# RC_Transmitter_RX_v42.net
KiCad netlist of a schematic drawn in EAGLE
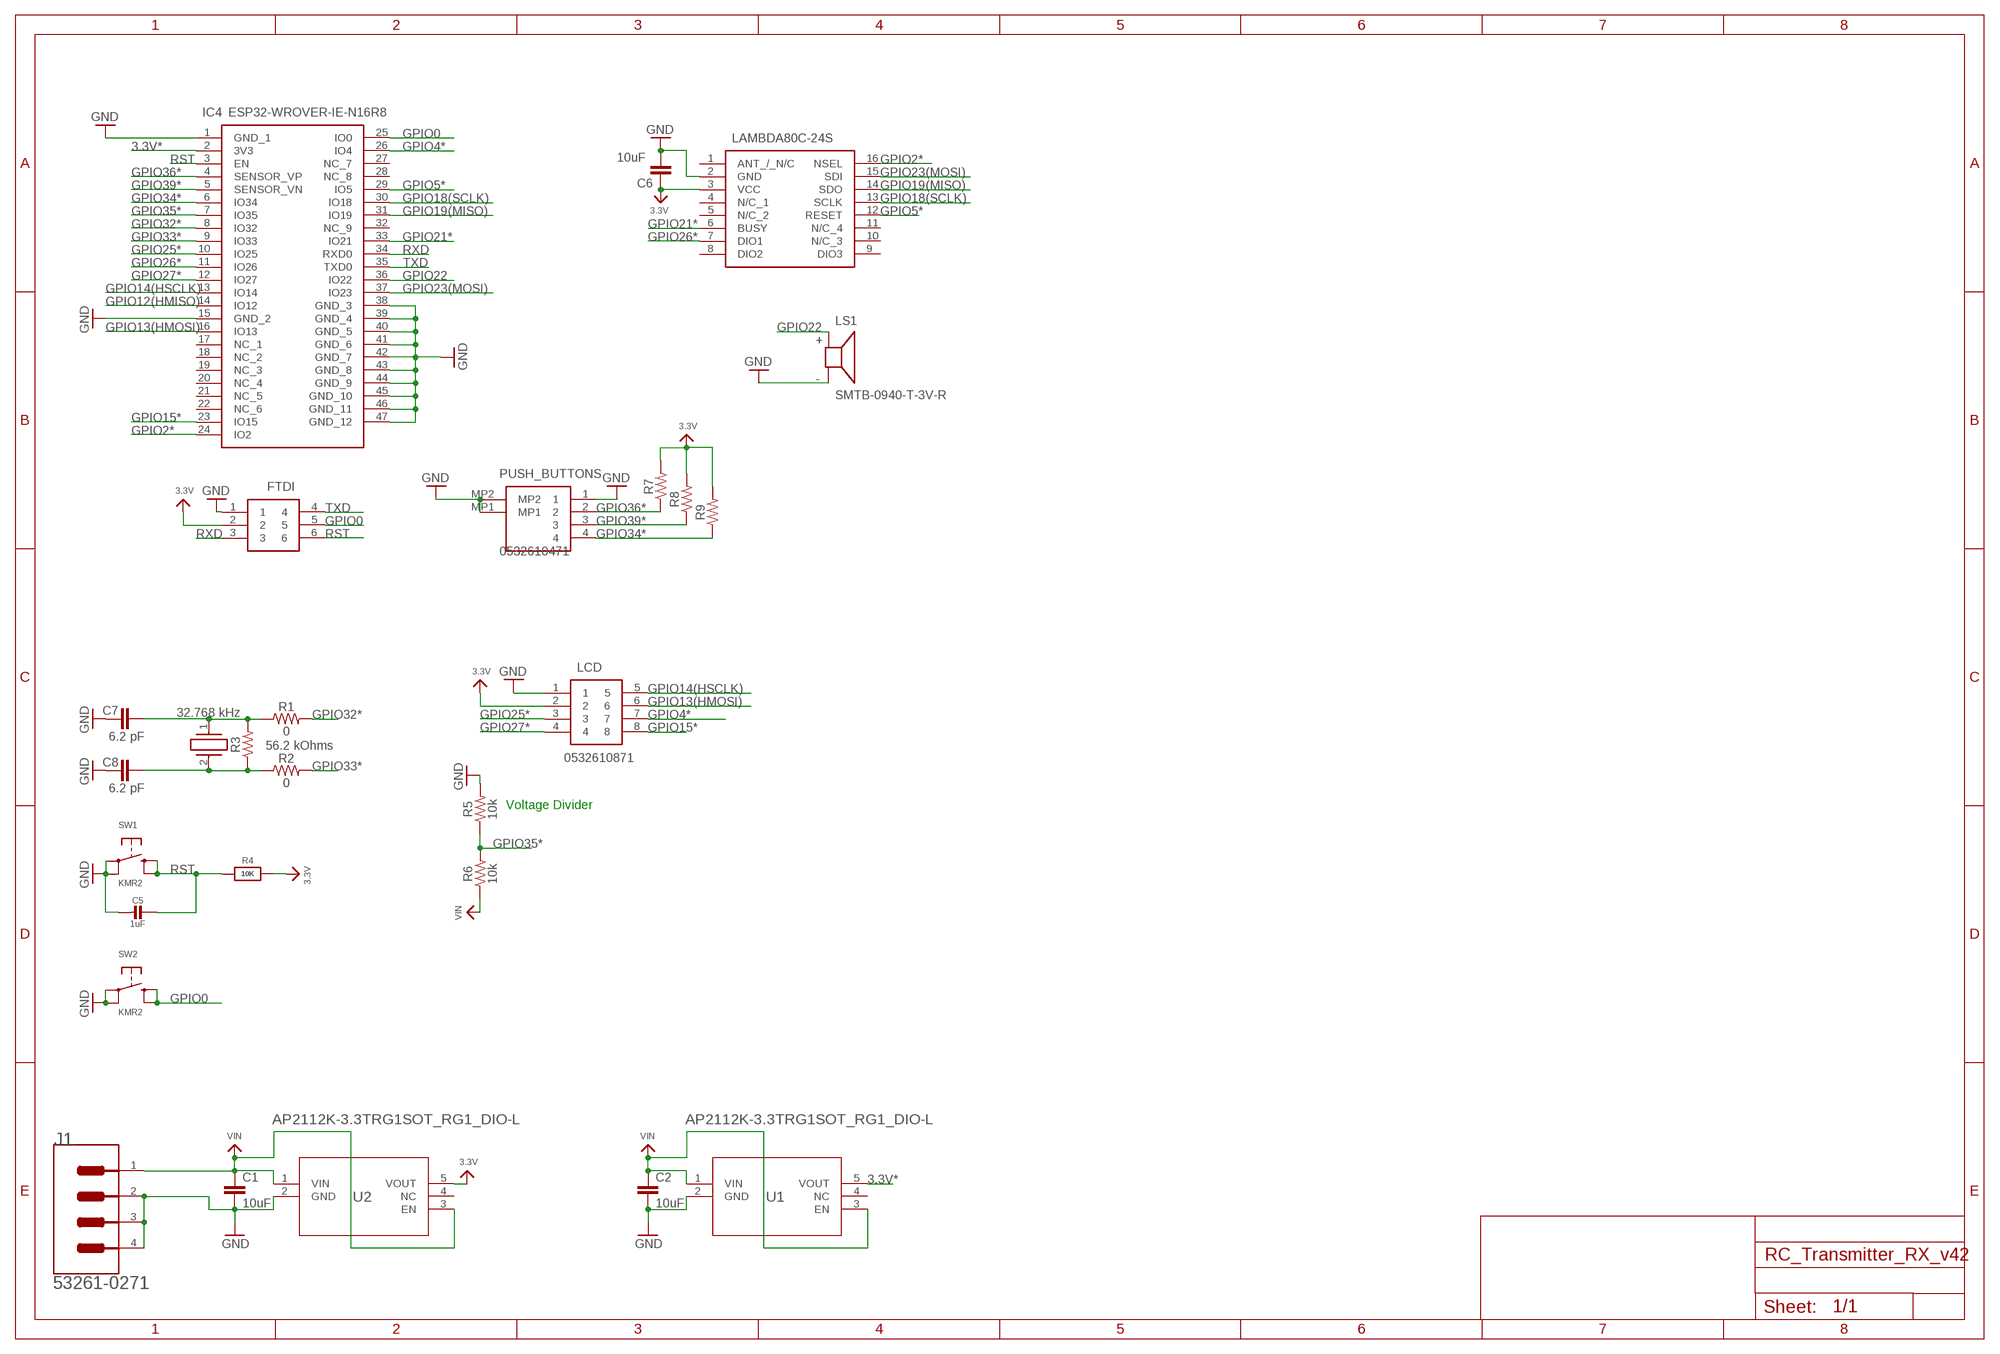
[diagram p0: schematic, sheet 1]

(export (version "E")
  (design (tool "Eeschema 10.0.6"))
  (components
    (comp (ref "C1")
      (value "10uF")
      (footprint "eagle-import:0805")
      (libsource (lib "eagle-import") (part "10UF-0805-10V-10%"))
    )
    (comp (ref "C2")
      (value "10uF")
      (footprint "eagle-import:0805")
      (libsource (lib "eagle-import") (part "10UF-0805-10V-10%"))
    )
    (comp (ref "C5")
      (value "1uF")
      (footprint "eagle-import:0805-NO")
      (libsource (lib "eagle-import") (part "CAP_CERAMIC0805-NOOUTLINE"))
    )
    (comp (ref "C6")
      (value "10uF")
      (footprint "eagle-import:0805")
      (libsource (lib "eagle-import") (part "10UF-0805-10V-10%"))
    )
    (comp (ref "C7")
      (value "6.2 pF")
      (footprint "eagle-import:CAPC2012X110")
      (libsource (lib "eagle-import") (part "CCHIP-0805(2012-METRIC)_"))
    )
    (comp (ref "C8")
      (value "6.2 pF")
      (footprint "eagle-import:CAPC2012X110")
      (libsource (lib "eagle-import") (part "CCHIP-0805(2012-METRIC)_"))
    )
    (comp (ref "CRYSTAL")
      (value "32.768 kHz")
      (footprint "eagle-import:ECX327CDX1293")
      (fields
        (field (name "ARROW_PART_NUMBER") "ECX-.327-CDX-1293")
        (field (name "MOUSER_PART_NUMBER") "520-ECX-.327CDX-1293")
        (field (name "ARROW_PART_NUMBER_1") "Crystal")
      )
      (libsource (lib "eagle-import") (part "ECX-.327-CDX-1293"))
    )
    (comp (ref "FTDI")
      (value "0532610671")
      (footprint "eagle-import:0532610671")
      (libsource (lib "eagle-import") (part "0532610671"))
    )
    (comp (ref "IC1")
      (value "LAMBDA80C-24S")
      (footprint "eagle-import:LAMBDA80C24S")
      (fields (field (name "MOUSER_PART_NUMBER") "223-LAMBDA80C-24S"))
      (libsource (lib "eagle-import") (part "LAMBDA80C-24S"))
    )
    (comp (ref "IC4")
      (value "ESP32-WROVER-IE-N16R8")
      (footprint "eagle-import:ESP32WROVERIEN16R8")
      (fields
        (field (name "MANUFACTURER_PART_NUMBER") "ESP32-Wrover-IE-N16R8")
        (field (name "MOUSER_PART_NUMBER") "356-ESP32WRVIE2864UC")
      )
      (libsource (lib "eagle-import") (part "ESP32-WROVER-IE-N16R8"))
    )
    (comp (ref "J1")
      (value "MOLEX_53261-0271MOLEX_53261-0271_0_0")
      (footprint "eagle-import:MOLEX_53261-0271_0")
      (fields
        (field (name "DIGIKEY_PART_NUMBER") "WM7620CT-ND")
        (field (name "MF") "Molex")
        (field (name "MOUSER_PART_NUMBER") "538-53261-0271")
      )
      (libsource (lib "eagle-import") (part "MOLEX_53261-0271MOLEX_53261-0271_0_0"))
    )
    (comp (ref "LCD")
      (value "0532610871")
      (footprint "eagle-import:53261-0871")
      (libsource (lib "eagle-import") (part "0532610871"))
    )
    (comp (ref "LS1")
      (value "SMTB-0940-T-3V-R")
      (footprint "eagle-import:XDCR_SMTB-0940-T-3V-R")
      (fields (field (name "MF") "PUI Audio, Inc."))
      (libsource (lib "eagle-import") (part "SMTB-0940-T-3V-R"))
    )
    (comp (ref "PUSH_BUTTONS")
      (value "0532610471")
      (footprint "eagle-import:0532610471")
      (libsource (lib "eagle-import") (part "0532610471"))
    )
    (comp (ref "R1")
      (value "0")
      (footprint "eagle-import:0603")
      (libsource (lib "eagle-import") (part "0OHM-0603-1/10W-5%"))
    )
    (comp (ref "R2")
      (value "0")
      (footprint "eagle-import:0603")
      (libsource (lib "eagle-import") (part "0OHM-0603-1/10W-5%"))
    )
    (comp (ref "R3")
      (value "56.2 kOhms")
      (footprint "eagle-import:0603")
      (libsource (lib "eagle-import") (part "0OHM-0603-1/10W-5%"))
    )
    (comp (ref "R4")
      (value "10K")
      (footprint "eagle-import:_0805")
      (libsource (lib "eagle-import") (part "RESISTOR_0805"))
    )
    (comp (ref "R5")
      (value "10k")
      (footprint "eagle-import:0603")
      (libsource (lib "eagle-import") (part "0OHM-0603-1/10W-5%"))
    )
    (comp (ref "R6")
      (value "10k")
      (footprint "eagle-import:0603")
      (libsource (lib "eagle-import") (part "0OHM-0603-1/10W-5%"))
    )
    (comp (ref "R7")
      (value "0")
      (footprint "eagle-import:0603")
      (libsource (lib "eagle-import") (part "0OHM-0603-1/10W-5%"))
    )
    (comp (ref "R8")
      (value "0")
      (footprint "eagle-import:0603")
      (libsource (lib "eagle-import") (part "0OHM-0603-1/10W-5%"))
    )
    (comp (ref "R9")
      (value "0")
      (footprint "eagle-import:0603")
      (libsource (lib "eagle-import") (part "0OHM-0603-1/10W-5%"))
    )
    (comp (ref "SW1")
      (value "KMR2")
      (footprint "eagle-import:BTN_KMR2_4.6X2.8")
      (libsource (lib "eagle-import") (part "SWITCH_TACT_SMT4.6X2.8"))
    )
    (comp (ref "SW2")
      (value "KMR2")
      (footprint "eagle-import:BTN_KMR2_4.6X2.8")
      (libsource (lib "eagle-import") (part "SWITCH_TACT_SMT4.6X2.8"))
    )
    (comp (ref "U1")
      (value "AP2112K-3.3TRG1SOT_RG1_DIO-L")
      (footprint "eagle-import:SOT_RG1_DIO-L")
      (fields
        (field (name "MANUFACTURER_PART_NUMBER") "AP2112K-3.3TRG1")
        (field (name "COPYRIGHT") "Copyright (C) 2023 Ultra Librarian. All rights reserved.")
      )
      (libsource (lib "eagle-import") (part "AP2112K-3.3TRG1SOT_RG1_DIO-L"))
    )
    (comp (ref "U2")
      (value "AP2112K-3.3TRG1SOT_RG1_DIO-L")
      (footprint "eagle-import:SOT_RG1_DIO-L")
      (fields
        (field (name "MANUFACTURER_PART_NUMBER") "AP2112K-3.3TRG1")
        (field (name "COPYRIGHT") "Copyright (C) 2023 Ultra Librarian. All rights reserved.")
      )
      (libsource (lib "eagle-import") (part "AP2112K-3.3TRG1SOT_RG1_DIO-L"))
    )
  )
  (nets
    (net (code "1") (name "/3.3V*") (class "Default")
      (node (ref "IC4") (pin "2") (pinfunction "3V3_2") (pintype "bidirectional"))
      (node (ref "U1") (pin "5") (pinfunction "VOUT_5") (pintype "passive"))
    )
    (net (code "2") (name "/GPIO0") (class "Default")
      (node (ref "FTDI") (pin "5") (pinfunction "5_5") (pintype "bidirectional"))
      (node (ref "IC4") (pin "25") (pinfunction "IO0_25") (pintype "bidirectional"))
      (node (ref "SW2") (pin "B") (pinfunction "S_B") (pintype "passive"))
      (node (ref "SW2") (pin "B'") (pinfunction "S1_B'") (pintype "passive"))
    )
    (net (code "3") (name "/GPIO2*") (class "Default")
      (node (ref "IC1") (pin "16") (pinfunction "NSEL_16") (pintype "bidirectional"))
      (node (ref "IC4") (pin "24") (pinfunction "IO2_24") (pintype "bidirectional"))
    )
    (net (code "4") (name "/GPIO4*") (class "Default")
      (node (ref "IC4") (pin "26") (pinfunction "IO4_26") (pintype "bidirectional"))
      (node (ref "LCD") (pin "7") (pinfunction "7_7") (pintype "bidirectional"))
    )
    (net (code "5") (name "/GPIO5*") (class "Default")
      (node (ref "IC1") (pin "12") (pinfunction "RESET_12") (pintype "bidirectional"))
      (node (ref "IC4") (pin "29") (pinfunction "IO5_29") (pintype "bidirectional"))
    )
    (net (code "6") (name "/GPIO12(HMISO)") (class "Default")
      (node (ref "IC4") (pin "14") (pinfunction "IO12_14") (pintype "bidirectional"))
    )
    (net (code "7") (name "/GPIO13(HMOSI)") (class "Default")
      (node (ref "IC4") (pin "16") (pinfunction "IO13_16") (pintype "bidirectional"))
      (node (ref "LCD") (pin "6") (pinfunction "6_6") (pintype "bidirectional"))
    )
    (net (code "8") (name "/GPIO14(HSCLK)") (class "Default")
      (node (ref "IC4") (pin "13") (pinfunction "IO14_13") (pintype "bidirectional"))
      (node (ref "LCD") (pin "5") (pinfunction "5_5") (pintype "bidirectional"))
    )
    (net (code "9") (name "/GPIO15*") (class "Default")
      (node (ref "IC4") (pin "23") (pinfunction "IO15_23") (pintype "bidirectional"))
      (node (ref "LCD") (pin "8") (pinfunction "8_8") (pintype "bidirectional"))
    )
    (net (code "10") (name "/GPIO18(SCLK)") (class "Default")
      (node (ref "IC1") (pin "13") (pinfunction "SCLK_13") (pintype "bidirectional"))
      (node (ref "IC4") (pin "30") (pinfunction "IO18_30") (pintype "bidirectional"))
    )
    (net (code "11") (name "/GPIO19(MISO)") (class "Default")
      (node (ref "IC1") (pin "14") (pinfunction "SDO_14") (pintype "bidirectional"))
      (node (ref "IC4") (pin "31") (pinfunction "IO19_31") (pintype "bidirectional"))
    )
    (net (code "12") (name "/GPIO21*") (class "Default")
      (node (ref "IC1") (pin "6") (pinfunction "BUSY_6") (pintype "bidirectional"))
      (node (ref "IC4") (pin "33") (pinfunction "IO21_33") (pintype "bidirectional"))
    )
    (net (code "13") (name "/GPIO22") (class "Default")
      (node (ref "IC4") (pin "36") (pinfunction "IO22_36") (pintype "bidirectional"))
      (node (ref "LS1") (pin "P") (pinfunction "P_P") (pintype "passive"))
    )
    (net (code "14") (name "/GPIO23(MOSI)") (class "Default")
      (node (ref "IC1") (pin "15") (pinfunction "SDI_15") (pintype "bidirectional"))
      (node (ref "IC4") (pin "37") (pinfunction "IO23_37") (pintype "bidirectional"))
    )
    (net (code "15") (name "/GPIO25*") (class "Default")
      (node (ref "IC4") (pin "10") (pinfunction "IO25_10") (pintype "bidirectional"))
      (node (ref "LCD") (pin "3") (pinfunction "3_3") (pintype "bidirectional"))
    )
    (net (code "16") (name "/GPIO26*") (class "Default")
      (node (ref "IC1") (pin "7") (pinfunction "DIO1_7") (pintype "bidirectional"))
      (node (ref "IC4") (pin "11") (pinfunction "IO26_11") (pintype "bidirectional"))
    )
    (net (code "17") (name "/GPIO27*") (class "Default")
      (node (ref "IC4") (pin "12") (pinfunction "IO27_12") (pintype "bidirectional"))
      (node (ref "LCD") (pin "4") (pinfunction "4_4") (pintype "bidirectional"))
    )
    (net (code "18") (name "/GPIO32*") (class "Default")
      (node (ref "IC4") (pin "8") (pinfunction "IO32_8") (pintype "bidirectional"))
      (node (ref "R1") (pin "2") (pinfunction "2_2") (pintype "passive"))
    )
    (net (code "19") (name "/GPIO33*") (class "Default")
      (node (ref "IC4") (pin "9") (pinfunction "IO33_9") (pintype "bidirectional"))
      (node (ref "R2") (pin "2") (pinfunction "2_2") (pintype "passive"))
    )
    (net (code "20") (name "/GPIO34*") (class "Default")
      (node (ref "IC4") (pin "6") (pinfunction "IO34_6") (pintype "bidirectional"))
      (node (ref "PUSH_BUTTONS") (pin "4") (pinfunction "4_4") (pintype "bidirectional"))
      (node (ref "R9") (pin "1") (pinfunction "1_1") (pintype "passive"))
    )
    (net (code "21") (name "/GPIO35*") (class "Default")
      (node (ref "IC4") (pin "7") (pinfunction "IO35_7") (pintype "bidirectional"))
      (node (ref "R5") (pin "1") (pinfunction "1_1") (pintype "passive"))
      (node (ref "R6") (pin "2") (pinfunction "2_2") (pintype "passive"))
    )
    (net (code "22") (name "/GPIO36*") (class "Default")
      (node (ref "IC4") (pin "4") (pinfunction "SENSOR_VP_4") (pintype "bidirectional"))
      (node (ref "PUSH_BUTTONS") (pin "2") (pinfunction "2_2") (pintype "bidirectional"))
      (node (ref "R7") (pin "1") (pinfunction "1_1") (pintype "passive"))
    )
    (net (code "23") (name "/GPIO39*") (class "Default")
      (node (ref "IC4") (pin "5") (pinfunction "SENSOR_VN_5") (pintype "bidirectional"))
      (node (ref "PUSH_BUTTONS") (pin "3") (pinfunction "3_3") (pintype "bidirectional"))
      (node (ref "R8") (pin "1") (pinfunction "1_1") (pintype "passive"))
    )
    (net (code "24") (name "/RST") (class "Default")
      (node (ref "C5") (pin "1") (pinfunction "1_1") (pintype "passive"))
      (node (ref "FTDI") (pin "6") (pinfunction "6_6") (pintype "bidirectional"))
      (node (ref "IC4") (pin "3") (pinfunction "EN_3") (pintype "bidirectional"))
      (node (ref "R4") (pin "1") (pinfunction "1_1") (pintype "passive"))
      (node (ref "SW1") (pin "B") (pinfunction "S_B") (pintype "passive"))
      (node (ref "SW1") (pin "B'") (pinfunction "S1_B'") (pintype "passive"))
    )
    (net (code "25") (name "/RXD") (class "Default")
      (node (ref "FTDI") (pin "3") (pinfunction "3_3") (pintype "bidirectional"))
      (node (ref "IC4") (pin "34") (pinfunction "RXD0_34") (pintype "bidirectional"))
    )
    (net (code "26") (name "/TXD") (class "Default")
      (node (ref "FTDI") (pin "4") (pinfunction "4_4") (pintype "bidirectional"))
      (node (ref "IC4") (pin "35") (pinfunction "TXD0_35") (pintype "bidirectional"))
    )
    (net (code "27") (name "3.3V") (class "Default")
      (node (ref "C6") (pin "1") (pinfunction "1_1") (pintype "passive"))
      (node (ref "FTDI") (pin "2") (pinfunction "2_2") (pintype "bidirectional"))
      (node (ref "IC1") (pin "3") (pinfunction "VCC_3") (pintype "bidirectional"))
      (node (ref "LCD") (pin "2") (pinfunction "2_2") (pintype "bidirectional"))
      (node (ref "R4") (pin "2") (pinfunction "2_2") (pintype "passive"))
      (node (ref "R7") (pin "2") (pinfunction "2_2") (pintype "passive"))
      (node (ref "R8") (pin "2") (pinfunction "2_2") (pintype "passive"))
      (node (ref "R9") (pin "2") (pinfunction "2_2") (pintype "passive"))
      (node (ref "U2") (pin "5") (pinfunction "VOUT_5") (pintype "passive"))
    )
    (net (code "28") (name "GND") (class "Default")
      (node (ref "C1") (pin "2") (pinfunction "2_2") (pintype "passive"))
      (node (ref "C2") (pin "2") (pinfunction "2_2") (pintype "passive"))
      (node (ref "C5") (pin "2") (pinfunction "2_2") (pintype "passive"))
      (node (ref "C6") (pin "2") (pinfunction "2_2") (pintype "passive"))
      (node (ref "C7") (pin "1") (pinfunction "1_1") (pintype "passive"))
      (node (ref "C8") (pin "1") (pinfunction "1_1") (pintype "passive"))
      (node (ref "FTDI") (pin "1") (pinfunction "1_1") (pintype "bidirectional"))
      (node (ref "IC1") (pin "2") (pinfunction "GND_2") (pintype "bidirectional"))
      (node (ref "IC4") (pin "1") (pinfunction "GND_1_1") (pintype "bidirectional"))
      (node (ref "IC4") (pin "15") (pinfunction "GND_2_15") (pintype "bidirectional"))
      (node (ref "IC4") (pin "38") (pinfunction "GND_3_38") (pintype "bidirectional"))
      (node (ref "IC4") (pin "39") (pinfunction "GND_4_39") (pintype "bidirectional"))
      (node (ref "IC4") (pin "40") (pinfunction "GND_5_40") (pintype "bidirectional"))
      (node (ref "IC4") (pin "41") (pinfunction "GND_6_41") (pintype "bidirectional"))
      (node (ref "IC4") (pin "42") (pinfunction "GND_7_42") (pintype "bidirectional"))
      (node (ref "IC4") (pin "43") (pinfunction "GND_8_43") (pintype "bidirectional"))
      (node (ref "IC4") (pin "44") (pinfunction "GND_9_44") (pintype "bidirectional"))
      (node (ref "IC4") (pin "45") (pinfunction "GND_10_45") (pintype "bidirectional"))
      (node (ref "IC4") (pin "46") (pinfunction "GND_11_46") (pintype "bidirectional"))
      (node (ref "IC4") (pin "47") (pinfunction "GND_12_47") (pintype "bidirectional"))
      (node (ref "J1") (pin "2") (pinfunction "2_2") (pintype "bidirectional"))
      (node (ref "J1") (pin "3") (pinfunction "MNT_1_3") (pintype "bidirectional"))
      (node (ref "J1") (pin "4") (pinfunction "MNT_2_4") (pintype "bidirectional"))
      (node (ref "LCD") (pin "1") (pinfunction "1_1") (pintype "bidirectional"))
      (node (ref "LS1") (pin "N") (pinfunction "N_N") (pintype "passive"))
      (node (ref "PUSH_BUTTONS") (pin "1") (pinfunction "1_1") (pintype "bidirectional"))
      (node (ref "PUSH_BUTTONS") (pin "MP1") (pinfunction "MP1_MP1") (pintype "bidirectional"))
      (node (ref "PUSH_BUTTONS") (pin "MP2") (pinfunction "MP2_MP2") (pintype "bidirectional"))
      (node (ref "R5") (pin "2") (pinfunction "2_2") (pintype "passive"))
      (node (ref "SW1") (pin "A") (pinfunction "P_A") (pintype "passive"))
      (node (ref "SW1") (pin "A'") (pinfunction "P1_A'") (pintype "passive"))
      (node (ref "SW2") (pin "A") (pinfunction "P_A") (pintype "passive"))
      (node (ref "SW2") (pin "A'") (pinfunction "P1_A'") (pintype "passive"))
      (node (ref "U1") (pin "2") (pinfunction "GND_2") (pintype "passive"))
      (node (ref "U2") (pin "2") (pinfunction "GND_2") (pintype "passive"))
    )
    (net (code "29") (name "Net-(CRYSTAL-X1)") (class "Default")
      (node (ref "C7") (pin "2") (pinfunction "2_2") (pintype "passive"))
      (node (ref "CRYSTAL") (pin "1") (pinfunction "X1_1") (pintype "bidirectional"))
      (node (ref "R1") (pin "1") (pinfunction "1_1") (pintype "passive"))
      (node (ref "R3") (pin "2") (pinfunction "2_2") (pintype "passive"))
    )
    (net (code "30") (name "Net-(CRYSTAL-X2)") (class "Default")
      (node (ref "C8") (pin "2") (pinfunction "2_2") (pintype "passive"))
      (node (ref "CRYSTAL") (pin "2") (pinfunction "X2_2") (pintype "bidirectional"))
      (node (ref "R2") (pin "1") (pinfunction "1_1") (pintype "passive"))
      (node (ref "R3") (pin "1") (pinfunction "1_1") (pintype "passive"))
    )
    (net (code "31") (name "VIN") (class "Default")
      (node (ref "C1") (pin "1") (pinfunction "1_1") (pintype "passive"))
      (node (ref "C2") (pin "1") (pinfunction "1_1") (pintype "passive"))
      (node (ref "J1") (pin "1") (pinfunction "1_1") (pintype "bidirectional"))
      (node (ref "R6") (pin "1") (pinfunction "1_1") (pintype "passive"))
      (node (ref "U1") (pin "1") (pinfunction "VIN_1") (pintype "passive"))
      (node (ref "U1") (pin "3") (pinfunction "EN_3") (pintype "passive"))
      (node (ref "U2") (pin "1") (pinfunction "VIN_1") (pintype "passive"))
      (node (ref "U2") (pin "3") (pinfunction "EN_3") (pintype "passive"))
    )
    (net (code "32") (name "unconnected-(IC1-ANT_{slash}_N{slash}C-Pad1)") (class "Default")
      (node (ref "IC1") (pin "1") (pinfunction "ANT_/_N/C_1") (pintype "bidirectional"))
    )
    (net (code "33") (name "unconnected-(IC1-DIO2-Pad8)") (class "Default")
      (node (ref "IC1") (pin "8") (pinfunction "DIO2_8") (pintype "bidirectional"))
    )
    (net (code "34") (name "unconnected-(IC1-DIO3-Pad9)") (class "Default")
      (node (ref "IC1") (pin "9") (pinfunction "DIO3_9") (pintype "bidirectional"))
    )
    (net (code "35") (name "unconnected-(IC1-N{slash}C_1-Pad4)") (class "Default")
      (node (ref "IC1") (pin "4") (pinfunction "N/C_1_4") (pintype "bidirectional"))
    )
    (net (code "36") (name "unconnected-(IC1-N{slash}C_2-Pad5)") (class "Default")
      (node (ref "IC1") (pin "5") (pinfunction "N/C_2_5") (pintype "bidirectional"))
    )
    (net (code "37") (name "unconnected-(IC1-N{slash}C_3-Pad10)") (class "Default")
      (node (ref "IC1") (pin "10") (pinfunction "N/C_3_10") (pintype "bidirectional"))
    )
    (net (code "38") (name "unconnected-(IC1-N{slash}C_4-Pad11)") (class "Default")
      (node (ref "IC1") (pin "11") (pinfunction "N/C_4_11") (pintype "bidirectional"))
    )
    (net (code "39") (name "unconnected-(IC4-NC_1-Pad17)") (class "Default")
      (node (ref "IC4") (pin "17") (pinfunction "NC_1_17") (pintype "bidirectional"))
    )
    (net (code "40") (name "unconnected-(IC4-NC_2-Pad18)") (class "Default")
      (node (ref "IC4") (pin "18") (pinfunction "NC_2_18") (pintype "bidirectional"))
    )
    (net (code "41") (name "unconnected-(IC4-NC_3-Pad19)") (class "Default")
      (node (ref "IC4") (pin "19") (pinfunction "NC_3_19") (pintype "bidirectional"))
    )
    (net (code "42") (name "unconnected-(IC4-NC_4-Pad20)") (class "Default")
      (node (ref "IC4") (pin "20") (pinfunction "NC_4_20") (pintype "bidirectional"))
    )
    (net (code "43") (name "unconnected-(IC4-NC_5-Pad21)") (class "Default")
      (node (ref "IC4") (pin "21") (pinfunction "NC_5_21") (pintype "bidirectional"))
    )
    (net (code "44") (name "unconnected-(IC4-NC_6-Pad22)") (class "Default")
      (node (ref "IC4") (pin "22") (pinfunction "NC_6_22") (pintype "bidirectional"))
    )
    (net (code "45") (name "unconnected-(IC4-NC_7-Pad27)") (class "Default")
      (node (ref "IC4") (pin "27") (pinfunction "NC_7_27") (pintype "bidirectional"))
    )
    (net (code "46") (name "unconnected-(IC4-NC_8-Pad28)") (class "Default")
      (node (ref "IC4") (pin "28") (pinfunction "NC_8_28") (pintype "bidirectional"))
    )
    (net (code "47") (name "unconnected-(IC4-NC_9-Pad32)") (class "Default")
      (node (ref "IC4") (pin "32") (pinfunction "NC_9_32") (pintype "bidirectional"))
    )
    (net (code "48") (name "unconnected-(U1-NC-Pad4)") (class "Default")
      (node (ref "U1") (pin "4") (pinfunction "NC_4") (pintype "passive"))
    )
    (net (code "49") (name "unconnected-(U2-NC-Pad4)") (class "Default")
      (node (ref "U2") (pin "4") (pinfunction "NC_4") (pintype "passive"))
    )
  )
)
